# USB-C-Control.net
KiCad netlist of a schematic drawn in Altium Designer
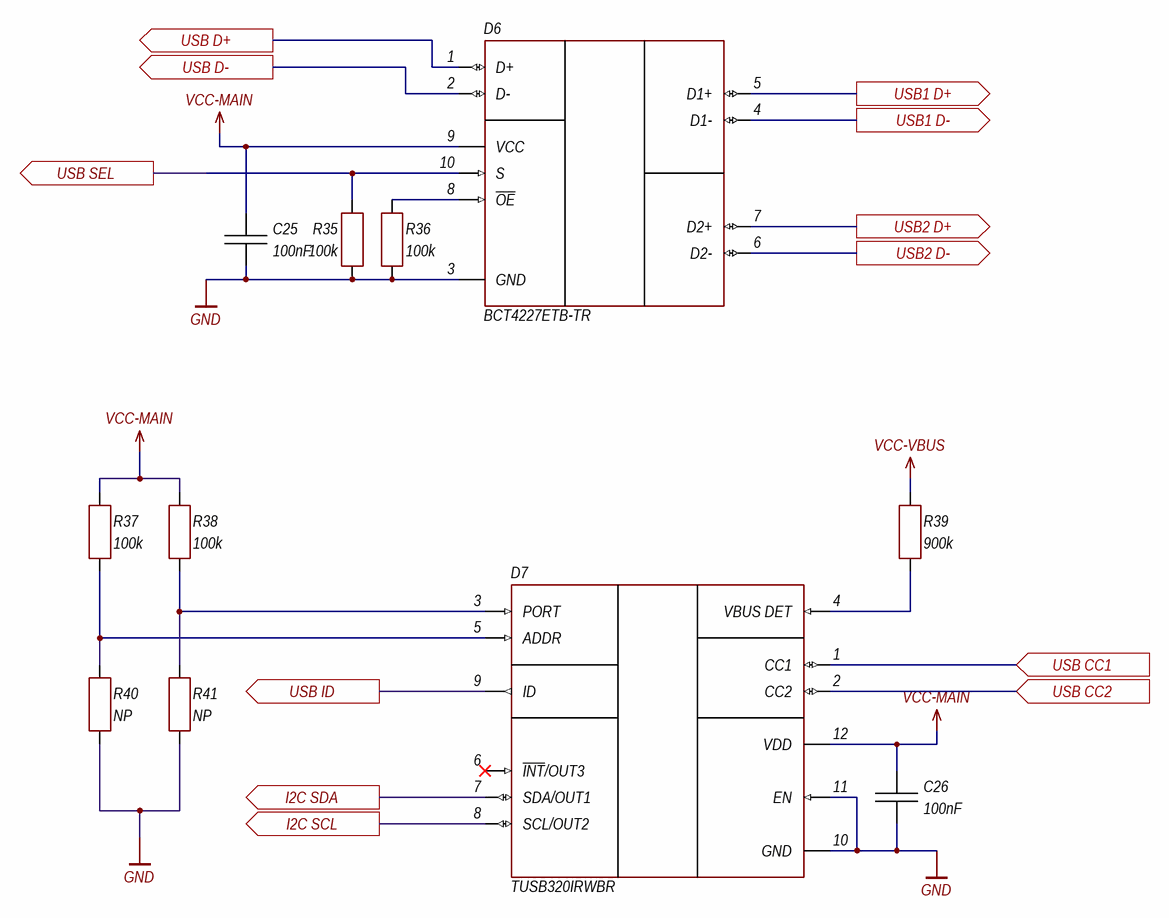
[diagram p0: USB-C-Control.SchDoc]

(export (version "E")
  (design (tool "Eeschema 10.0.6"))
  (components
    (comp (ref "C25") (value "100nF") (footprint "CH0402C") (libsource (lib "Discrete") (part "Capacitor")))
    (comp (ref "C26") (value "100nF") (footprint "CH0402C") (libsource (lib "Discrete") (part "Capacitor")))
    (comp (ref "D6")
      (value "BCT4227ETB-TR")
      (footprint "10-UQFN")
      (description "USB 2.0 1:2 Mux/Demux")
      (fields (field (name "MANUFACTURER") "BROADCHIP") (field (name "MODEL") "BCT4227ETB-TR"))
      (libsource (lib "Interface") (part "BCT4227ETB-TR"))
    )
    (comp (ref "D7")
      (value "TUSB320IRWBR")
      (footprint "12-X2QFN")
      (description "USB-C Port I2C controller (USB OTG)")
      (fields (field (name "MANUFACTURER") "Texas Instruments") (field (name "MODEL") "TUSB320IRWBR"))
      (libsource (lib "Interface") (part "TUSB320"))
    )
    (comp (ref "R35") (value "100k") (footprint "CH0402R") (libsource (lib "") (part "Resistor_1")))
    (comp (ref "R36") (value "100k") (footprint "CH0402R") (libsource (lib "Discrete") (part "Resistor")))
    (comp (ref "R37") (value "100k") (footprint "CH0402R") (libsource (lib "Discrete") (part "Resistor")))
    (comp (ref "R38") (value "100k") (footprint "CH0402R") (libsource (lib "Discrete") (part "Resistor")))
    (comp (ref "R39") (value "900k") (footprint "CH0402R") (libsource (lib "Discrete") (part "Resistor")))
    (comp (ref "R40") (value "NP") (footprint "CH0402R") (libsource (lib "Discrete") (part "Resistor")))
    (comp (ref "R41") (value "NP") (footprint "CH0402R") (libsource (lib "Discrete") (part "Resistor")))
  )
  (nets
    (net (code "1") (name "/I2C SCL") (class "Default")
      (node (ref "D7") (pin "8") (pinfunction "SCL/OUT2_8") (pintype "bidirectional"))
    )
    (net (code "2") (name "/I2C SDA") (class "Default")
      (node (ref "D7") (pin "7") (pinfunction "SDA/OUT1_7") (pintype "bidirectional"))
    )
    (net (code "3") (name "/USB CC1") (class "Default")
      (node (ref "D7") (pin "1") (pinfunction "CC1_1") (pintype "bidirectional"))
    )
    (net (code "4") (name "/USB CC2") (class "Default")
      (node (ref "D7") (pin "2") (pinfunction "CC2_2") (pintype "bidirectional"))
    )
    (net (code "5") (name "/USB D+") (class "Default")
      (node (ref "D6") (pin "1") (pinfunction "D+_1") (pintype "bidirectional"))
    )
    (net (code "6") (name "/USB D-") (class "Default")
      (node (ref "D6") (pin "2") (pinfunction "D-_2") (pintype "bidirectional"))
    )
    (net (code "7") (name "/USB ID") (class "Default")
      (node (ref "D7") (pin "9") (pinfunction "ID_9") (pintype "output"))
    )
    (net (code "8") (name "/USB SEL") (class "Default")
      (node (ref "D6") (pin "10") (pinfunction "S_10") (pintype "input"))
      (node (ref "R35") (pin "2") (pinfunction "2_2") (pintype "passive"))
    )
    (net (code "9") (name "/USB1 D+") (class "Default")
      (node (ref "D6") (pin "5") (pinfunction "D1+_5") (pintype "bidirectional"))
    )
    (net (code "10") (name "/USB1 D-") (class "Default")
      (node (ref "D6") (pin "4") (pinfunction "D1-_4") (pintype "bidirectional"))
    )
    (net (code "11") (name "/USB2 D+") (class "Default")
      (node (ref "D6") (pin "7") (pinfunction "D2+_7") (pintype "bidirectional"))
    )
    (net (code "12") (name "/USB2 D-") (class "Default")
      (node (ref "D6") (pin "6") (pinfunction "D2-_6") (pintype "bidirectional"))
    )
    (net (code "13") (name "GND") (class "Default")
      (node (ref "C25") (pin "1") (pinfunction "1_1") (pintype "passive"))
      (node (ref "C26") (pin "1") (pinfunction "1_1") (pintype "passive"))
      (node (ref "D6") (pin "3") (pinfunction "GND_3") (pintype "power_in"))
      (node (ref "D7") (pin "10") (pinfunction "GND_10") (pintype "power_in"))
      (node (ref "D7") (pin "11") (pinfunction "EN_11") (pintype "input"))
      (node (ref "R35") (pin "1") (pinfunction "1_1") (pintype "passive"))
      (node (ref "R36") (pin "1") (pinfunction "1_1") (pintype "passive"))
      (node (ref "R40") (pin "1") (pinfunction "1_1") (pintype "passive"))
      (node (ref "R41") (pin "1") (pinfunction "1_1") (pintype "passive"))
    )
    (net (code "14") (name "Net-(D6-~{OE})") (class "Default")
      (node (ref "D6") (pin "8") (pinfunction "~{OE}_8") (pintype "input"))
      (node (ref "R36") (pin "2") (pinfunction "2_2") (pintype "passive"))
    )
    (net (code "15") (name "Net-(D7-ADDR)") (class "Default")
      (node (ref "D7") (pin "5") (pinfunction "ADDR_5") (pintype "input"))
      (node (ref "R37") (pin "1") (pinfunction "1_1") (pintype "passive"))
      (node (ref "R40") (pin "2") (pinfunction "2_2") (pintype "passive"))
    )
    (net (code "16") (name "Net-(D7-PORT)") (class "Default")
      (node (ref "D7") (pin "3") (pinfunction "PORT_3") (pintype "input"))
      (node (ref "R38") (pin "1") (pinfunction "1_1") (pintype "passive"))
      (node (ref "R41") (pin "2") (pinfunction "2_2") (pintype "passive"))
    )
    (net (code "17") (name "Net-(D7-VBUS_DET)") (class "Default")
      (node (ref "D7") (pin "4") (pinfunction "VBUS_DET_4") (pintype "input"))
      (node (ref "R39") (pin "1") (pinfunction "1_1") (pintype "passive"))
    )
    (net (code "18") (name "VCC-MAIN") (class "Default")
      (node (ref "C25") (pin "2") (pinfunction "2_2") (pintype "passive"))
      (node (ref "C26") (pin "2") (pinfunction "2_2") (pintype "passive"))
      (node (ref "D6") (pin "9") (pinfunction "VCC_9") (pintype "power_in"))
      (node (ref "D7") (pin "12") (pinfunction "VDD_12") (pintype "power_in"))
      (node (ref "R37") (pin "2") (pinfunction "2_2") (pintype "passive"))
      (node (ref "R38") (pin "2") (pinfunction "2_2") (pintype "passive"))
    )
    (net (code "19") (name "VCC-VBUS") (class "Default")
      (node (ref "R39") (pin "2") (pinfunction "2_2") (pintype "passive"))
    )
    (net (code "20") (name "unconnected-(D7-~{INT}{slash}OUT3-Pad6)") (class "Default")
      (node (ref "D7") (pin "6") (pinfunction "~{INT}/OUT3_6") (pintype "input+no_connect"))
    )
  )
)
